# MDL-485.net
KiCad netlist of a schematic drawn in Altium Designer
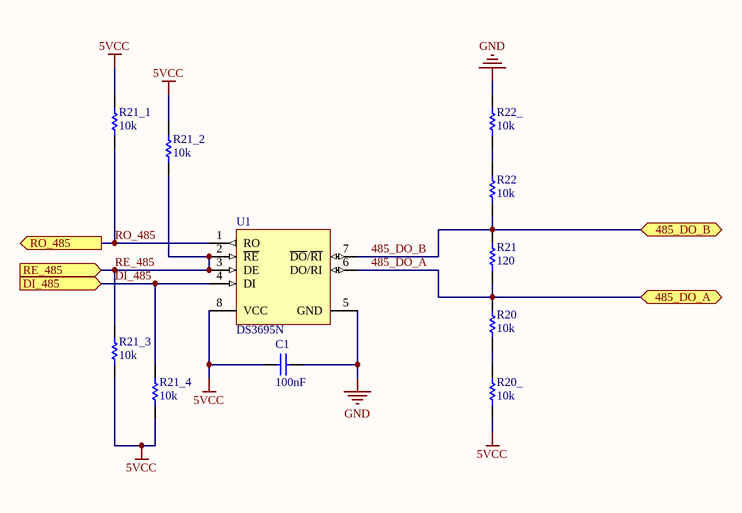
[diagram p0: MDL-485.SchDoc]

(export (version "E")
  (design (tool "Eeschema 10.0.6"))
  (components
    (comp (ref "C1")
      (value "100nF")
      (footprint "VP44-2.5")
      (description "Dipped Radial Multilayer Ceramic Capacitor X7R: 220nF, 100V")
      (fields (field (name "Comment") "VP44BY224JB") (field (name "PUBLISHER") "Altium Limited"))
      (libsource (lib "Vishay Vitramon Ceramic Dipped Capacitor") (part "VP44BY224JB"))
    )
    (comp (ref "R20")
      (value "10k")
      (footprint "AXIAL-0.3")
      (description "Resistor")
      (fields (field (name "Comment") "Res1") (field (name "PUBLISHER") "Altium Limited"))
      (libsource (lib "Miscellaneous Devices") (part "Res1"))
    )
    (comp (ref "R20_")
      (value "10k")
      (footprint "AXIAL-0.3")
      (description "Resistor")
      (fields (field (name "Comment") "Res1") (field (name "PUBLISHER") "Altium Limited"))
      (libsource (lib "Miscellaneous Devices") (part "Res1"))
    )
    (comp (ref "R21")
      (value "120")
      (footprint "AXIAL-0.3")
      (description "Resistor")
      (fields (field (name "Comment") "Res1") (field (name "PUBLISHER") "Altium Limited"))
      (libsource (lib "Miscellaneous Devices") (part "Res1"))
    )
    (comp (ref "R21_1")
      (value "10k")
      (footprint "AXIAL-0.3")
      (description "Resistor")
      (fields (field (name "Comment") "Res1") (field (name "PUBLISHER") "Altium Limited"))
      (libsource (lib "Miscellaneous Devices") (part "Res1"))
    )
    (comp (ref "R21_2")
      (value "10k")
      (footprint "AXIAL-0.3")
      (description "Resistor")
      (fields (field (name "Comment") "Res1") (field (name "PUBLISHER") "Altium Limited"))
      (libsource (lib "Miscellaneous Devices") (part "Res1"))
    )
    (comp (ref "R21_3")
      (value "10k")
      (footprint "AXIAL-0.3")
      (description "Resistor")
      (fields (field (name "Comment") "Res1") (field (name "PUBLISHER") "Altium Limited"))
      (libsource (lib "Miscellaneous Devices") (part "Res1"))
    )
    (comp (ref "R21_4")
      (value "10k")
      (footprint "AXIAL-0.3")
      (description "Resistor")
      (fields (field (name "Comment") "Res1") (field (name "PUBLISHER") "Altium Limited"))
      (libsource (lib "Miscellaneous Devices") (part "Res1"))
    )
    (comp (ref "R22")
      (value "10k")
      (footprint "AXIAL-0.3")
      (description "Resistor")
      (fields (field (name "Comment") "Res1") (field (name "PUBLISHER") "Altium Limited"))
      (libsource (lib "Miscellaneous Devices") (part "Res1"))
    )
    (comp (ref "R22_")
      (value "10k")
      (footprint "AXIAL-0.3")
      (description "Resistor")
      (fields (field (name "Comment") "Res1") (field (name "PUBLISHER") "Altium Limited"))
      (libsource (lib "Miscellaneous Devices") (part "Res1"))
    )
    (comp (ref "U1")
      (value "DS3695N")
      (footprint "N08E")
      (description "Multipoint RS485/RS422 Transceiver/Repeater")
      (fields
        (field (name "MANUFACTURER") "National Semiconductor")
        (field (name "DIGIKEYPARTNUMBER") "DS3695N-ND")
        (field (name "PUBLISHER") "Altium Limited")
      )
      (libsource (lib "NSC Interface") (part "DS3695N"))
    )
  )
  (nets
    (net (code "1") (name "/485_DO_A") (class "Default")
      (node (ref "R20") (pin "2") (pinfunction "2_2") (pintype "passive"))
      (node (ref "R21") (pin "1") (pinfunction "1_1") (pintype "passive"))
      (node (ref "U1") (pin "6") (pinfunction "DO/RI_6") (pintype "bidirectional"))
    )
    (net (code "2") (name "/485_DO_B") (class "Default")
      (node (ref "R21") (pin "2") (pinfunction "2_2") (pintype "passive"))
      (node (ref "R22") (pin "1") (pinfunction "1_1") (pintype "passive"))
      (node (ref "U1") (pin "7") (pinfunction "~{DO}/~{RI}_7") (pintype "bidirectional"))
    )
    (net (code "3") (name "/DI_485") (class "Default")
      (node (ref "R21_2") (pin "1") (pinfunction "1_1") (pintype "passive"))
      (node (ref "R21_3") (pin "2") (pinfunction "2_2") (pintype "passive"))
      (node (ref "R21_4") (pin "2") (pinfunction "2_2") (pintype "passive"))
      (node (ref "U1") (pin "2") (pinfunction "~{RE}_2") (pintype "input"))
      (node (ref "U1") (pin "3") (pinfunction "DE_3") (pintype "input"))
      (node (ref "U1") (pin "4") (pinfunction "DI_4") (pintype "input"))
    )
    (net (code "4") (name "/RO_485") (class "Default")
      (node (ref "R21_1") (pin "1") (pinfunction "1_1") (pintype "passive"))
      (node (ref "U1") (pin "1") (pinfunction "RO_1") (pintype "output"))
    )
    (net (code "5") (name "5VCC") (class "Default")
      (node (ref "C1") (pin "1") (pinfunction "1_1") (pintype "passive"))
      (node (ref "R20_") (pin "1") (pinfunction "1_1") (pintype "passive"))
      (node (ref "R21_1") (pin "2") (pinfunction "2_2") (pintype "passive"))
      (node (ref "R21_2") (pin "2") (pinfunction "2_2") (pintype "passive"))
      (node (ref "R21_3") (pin "1") (pinfunction "1_1") (pintype "passive"))
      (node (ref "R21_4") (pin "1") (pinfunction "1_1") (pintype "passive"))
      (node (ref "U1") (pin "8") (pinfunction "VCC_8") (pintype "power_in"))
    )
    (net (code "6") (name "GND") (class "Default")
      (node (ref "C1") (pin "2") (pinfunction "2_2") (pintype "passive"))
      (node (ref "R22_") (pin "2") (pinfunction "2_2") (pintype "passive"))
      (node (ref "U1") (pin "5") (pinfunction "GND_5") (pintype "power_in"))
    )
    (net (code "7") (name "Net-(R20-Pad1)") (class "Default")
      (node (ref "R20") (pin "1") (pinfunction "1_1") (pintype "passive"))
      (node (ref "R20_") (pin "2") (pinfunction "2_2") (pintype "passive"))
    )
    (net (code "8") (name "Net-(R22-Pad2)") (class "Default")
      (node (ref "R22") (pin "2") (pinfunction "2_2") (pintype "passive"))
      (node (ref "R22_") (pin "1") (pinfunction "1_1") (pintype "passive"))
    )
  )
)
